# LED_Display_1_1.net
KiCad netlist of a schematic drawn in EAGLE
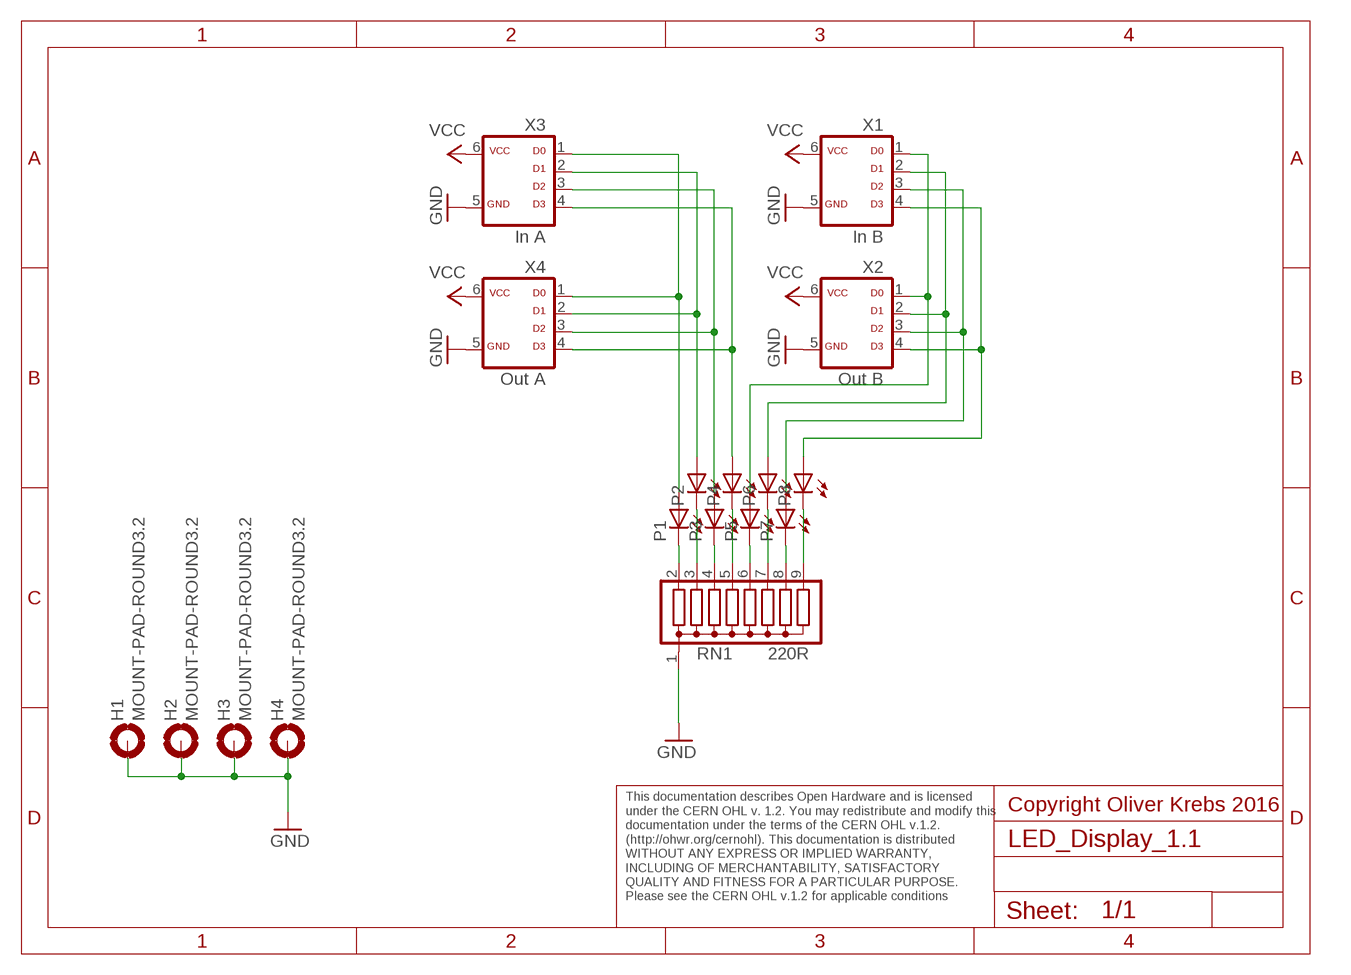
[diagram p0: schematic, sheet 1]

(export (version "E")
  (design (tool "Eeschema 10.0.6"))
  (components
    (comp (ref "H1")
      (value "MOUNT-PAD-ROUND3.2")
      (footprint "eagle-import:3,2-PAD")
      (libsource (lib "eagle-import") (part "MOUNT-PAD-ROUND3.2"))
    )
    (comp (ref "H2")
      (value "MOUNT-PAD-ROUND3.2")
      (footprint "eagle-import:3,2-PAD")
      (libsource (lib "eagle-import") (part "MOUNT-PAD-ROUND3.2"))
    )
    (comp (ref "H3")
      (value "MOUNT-PAD-ROUND3.2")
      (footprint "eagle-import:3,2-PAD")
      (libsource (lib "eagle-import") (part "MOUNT-PAD-ROUND3.2"))
    )
    (comp (ref "H4")
      (value "MOUNT-PAD-ROUND3.2")
      (footprint "eagle-import:3,2-PAD")
      (libsource (lib "eagle-import") (part "MOUNT-PAD-ROUND3.2"))
    )
    (comp (ref "P1")
      (value "LED3MM")
      (footprint "eagle-import:LED3MM")
      (libsource (lib "eagle-import") (part "LED3MM"))
    )
    (comp (ref "P2")
      (value "LED3MM")
      (footprint "eagle-import:LED3MM")
      (libsource (lib "eagle-import") (part "LED3MM"))
    )
    (comp (ref "P3")
      (value "LED3MM")
      (footprint "eagle-import:LED3MM")
      (libsource (lib "eagle-import") (part "LED3MM"))
    )
    (comp (ref "P4")
      (value "LED3MM")
      (footprint "eagle-import:LED3MM")
      (libsource (lib "eagle-import") (part "LED3MM"))
    )
    (comp (ref "P5")
      (value "LED3MM")
      (footprint "eagle-import:LED3MM")
      (libsource (lib "eagle-import") (part "LED3MM"))
    )
    (comp (ref "P6")
      (value "LED3MM")
      (footprint "eagle-import:LED3MM")
      (libsource (lib "eagle-import") (part "LED3MM"))
    )
    (comp (ref "P7")
      (value "LED3MM")
      (footprint "eagle-import:LED3MM")
      (libsource (lib "eagle-import") (part "LED3MM"))
    )
    (comp (ref "P8")
      (value "LED3MM")
      (footprint "eagle-import:LED3MM")
      (libsource (lib "eagle-import") (part "LED3MM"))
    )
    (comp (ref "RN1")
      (value "220R")
      (footprint "eagle-import:SIL9")
      (libsource (lib "eagle-import") (part "G08R"))
    )
    (comp (ref "X1")
      (value "In B")
      (footprint "eagle-import:ML-6")
      (libsource (lib "eagle-import") (part "ML6D"))
    )
    (comp (ref "X2")
      (value "Out B")
      (footprint "eagle-import:ML-6")
      (libsource (lib "eagle-import") (part "ML6D"))
    )
    (comp (ref "X3")
      (value "In A")
      (footprint "eagle-import:ML-6")
      (libsource (lib "eagle-import") (part "ML6D"))
    )
    (comp (ref "X4")
      (value "Out A")
      (footprint "eagle-import:ML-6")
      (libsource (lib "eagle-import") (part "ML6D"))
    )
  )
  (nets
    (net (code "1") (name "GND") (class "Default")
      (node (ref "H1") (pin "B3,2") (pinfunction "MOUNT_B3,2") (pintype "passive"))
      (node (ref "H2") (pin "B3,2") (pinfunction "MOUNT_B3,2") (pintype "passive"))
      (node (ref "H3") (pin "B3,2") (pinfunction "MOUNT_B3,2") (pintype "passive"))
      (node (ref "H4") (pin "B3,2") (pinfunction "MOUNT_B3,2") (pintype "passive"))
      (node (ref "RN1") (pin "1") (pinfunction "1_1") (pintype "passive"))
      (node (ref "X1") (pin "5") (pinfunction "5_5") (pintype "passive"))
      (node (ref "X2") (pin "5") (pinfunction "5_5") (pintype "passive"))
      (node (ref "X3") (pin "5") (pinfunction "5_5") (pintype "passive"))
      (node (ref "X4") (pin "5") (pinfunction "5_5") (pintype "passive"))
    )
    (net (code "2") (name "Net-(P1-C)") (class "Default")
      (node (ref "P1") (pin "K") (pinfunction "C_K") (pintype "passive"))
      (node (ref "RN1") (pin "2") (pinfunction "2_2") (pintype "passive"))
    )
    (net (code "3") (name "Net-(P1-PadA)") (class "Default")
      (node (ref "P1") (pin "A") (pinfunction "A_A") (pintype "passive"))
      (node (ref "X3") (pin "1") (pinfunction "1_1") (pintype "passive"))
      (node (ref "X4") (pin "1") (pinfunction "1_1") (pintype "passive"))
    )
    (net (code "4") (name "Net-(P2-C)") (class "Default")
      (node (ref "P2") (pin "K") (pinfunction "C_K") (pintype "passive"))
      (node (ref "RN1") (pin "3") (pinfunction "3_3") (pintype "passive"))
    )
    (net (code "5") (name "Net-(P2-PadA)") (class "Default")
      (node (ref "P2") (pin "A") (pinfunction "A_A") (pintype "passive"))
      (node (ref "X3") (pin "2") (pinfunction "2_2") (pintype "passive"))
      (node (ref "X4") (pin "2") (pinfunction "2_2") (pintype "passive"))
    )
    (net (code "6") (name "Net-(P3-C)") (class "Default")
      (node (ref "P3") (pin "K") (pinfunction "C_K") (pintype "passive"))
      (node (ref "RN1") (pin "4") (pinfunction "4_4") (pintype "passive"))
    )
    (net (code "7") (name "Net-(P3-PadA)") (class "Default")
      (node (ref "P3") (pin "A") (pinfunction "A_A") (pintype "passive"))
      (node (ref "X3") (pin "3") (pinfunction "3_3") (pintype "passive"))
      (node (ref "X4") (pin "3") (pinfunction "3_3") (pintype "passive"))
    )
    (net (code "8") (name "Net-(P4-C)") (class "Default")
      (node (ref "P4") (pin "K") (pinfunction "C_K") (pintype "passive"))
      (node (ref "RN1") (pin "5") (pinfunction "5_5") (pintype "passive"))
    )
    (net (code "9") (name "Net-(P4-PadA)") (class "Default")
      (node (ref "P4") (pin "A") (pinfunction "A_A") (pintype "passive"))
      (node (ref "X3") (pin "4") (pinfunction "4_4") (pintype "passive"))
      (node (ref "X4") (pin "4") (pinfunction "4_4") (pintype "passive"))
    )
    (net (code "10") (name "Net-(P5-C)") (class "Default")
      (node (ref "P5") (pin "K") (pinfunction "C_K") (pintype "passive"))
      (node (ref "RN1") (pin "6") (pinfunction "6_6") (pintype "passive"))
    )
    (net (code "11") (name "Net-(P5-PadA)") (class "Default")
      (node (ref "P5") (pin "A") (pinfunction "A_A") (pintype "passive"))
      (node (ref "X1") (pin "1") (pinfunction "1_1") (pintype "passive"))
      (node (ref "X2") (pin "1") (pinfunction "1_1") (pintype "passive"))
    )
    (net (code "12") (name "Net-(P6-C)") (class "Default")
      (node (ref "P6") (pin "K") (pinfunction "C_K") (pintype "passive"))
      (node (ref "RN1") (pin "7") (pinfunction "7_7") (pintype "passive"))
    )
    (net (code "13") (name "Net-(P6-PadA)") (class "Default")
      (node (ref "P6") (pin "A") (pinfunction "A_A") (pintype "passive"))
      (node (ref "X1") (pin "2") (pinfunction "2_2") (pintype "passive"))
      (node (ref "X2") (pin "2") (pinfunction "2_2") (pintype "passive"))
    )
    (net (code "14") (name "Net-(P7-C)") (class "Default")
      (node (ref "P7") (pin "K") (pinfunction "C_K") (pintype "passive"))
      (node (ref "RN1") (pin "8") (pinfunction "8_8") (pintype "passive"))
    )
    (net (code "15") (name "Net-(P7-PadA)") (class "Default")
      (node (ref "P7") (pin "A") (pinfunction "A_A") (pintype "passive"))
      (node (ref "X1") (pin "3") (pinfunction "3_3") (pintype "passive"))
      (node (ref "X2") (pin "3") (pinfunction "3_3") (pintype "passive"))
    )
    (net (code "16") (name "Net-(P8-C)") (class "Default")
      (node (ref "P8") (pin "K") (pinfunction "C_K") (pintype "passive"))
      (node (ref "RN1") (pin "9") (pinfunction "9_9") (pintype "passive"))
    )
    (net (code "17") (name "Net-(P8-PadA)") (class "Default")
      (node (ref "P8") (pin "A") (pinfunction "A_A") (pintype "passive"))
      (node (ref "X1") (pin "4") (pinfunction "4_4") (pintype "passive"))
      (node (ref "X2") (pin "4") (pinfunction "4_4") (pintype "passive"))
    )
    (net (code "18") (name "VCC") (class "Default")
      (node (ref "X1") (pin "6") (pinfunction "6_6") (pintype "passive"))
      (node (ref "X2") (pin "6") (pinfunction "6_6") (pintype "passive"))
      (node (ref "X3") (pin "6") (pinfunction "6_6") (pintype "passive"))
      (node (ref "X4") (pin "6") (pinfunction "6_6") (pintype "passive"))
    )
  )
)
